# RobotCtrl_V2_Mother-board_Power.net
KiCad netlist of a schematic drawn in Altium Designer
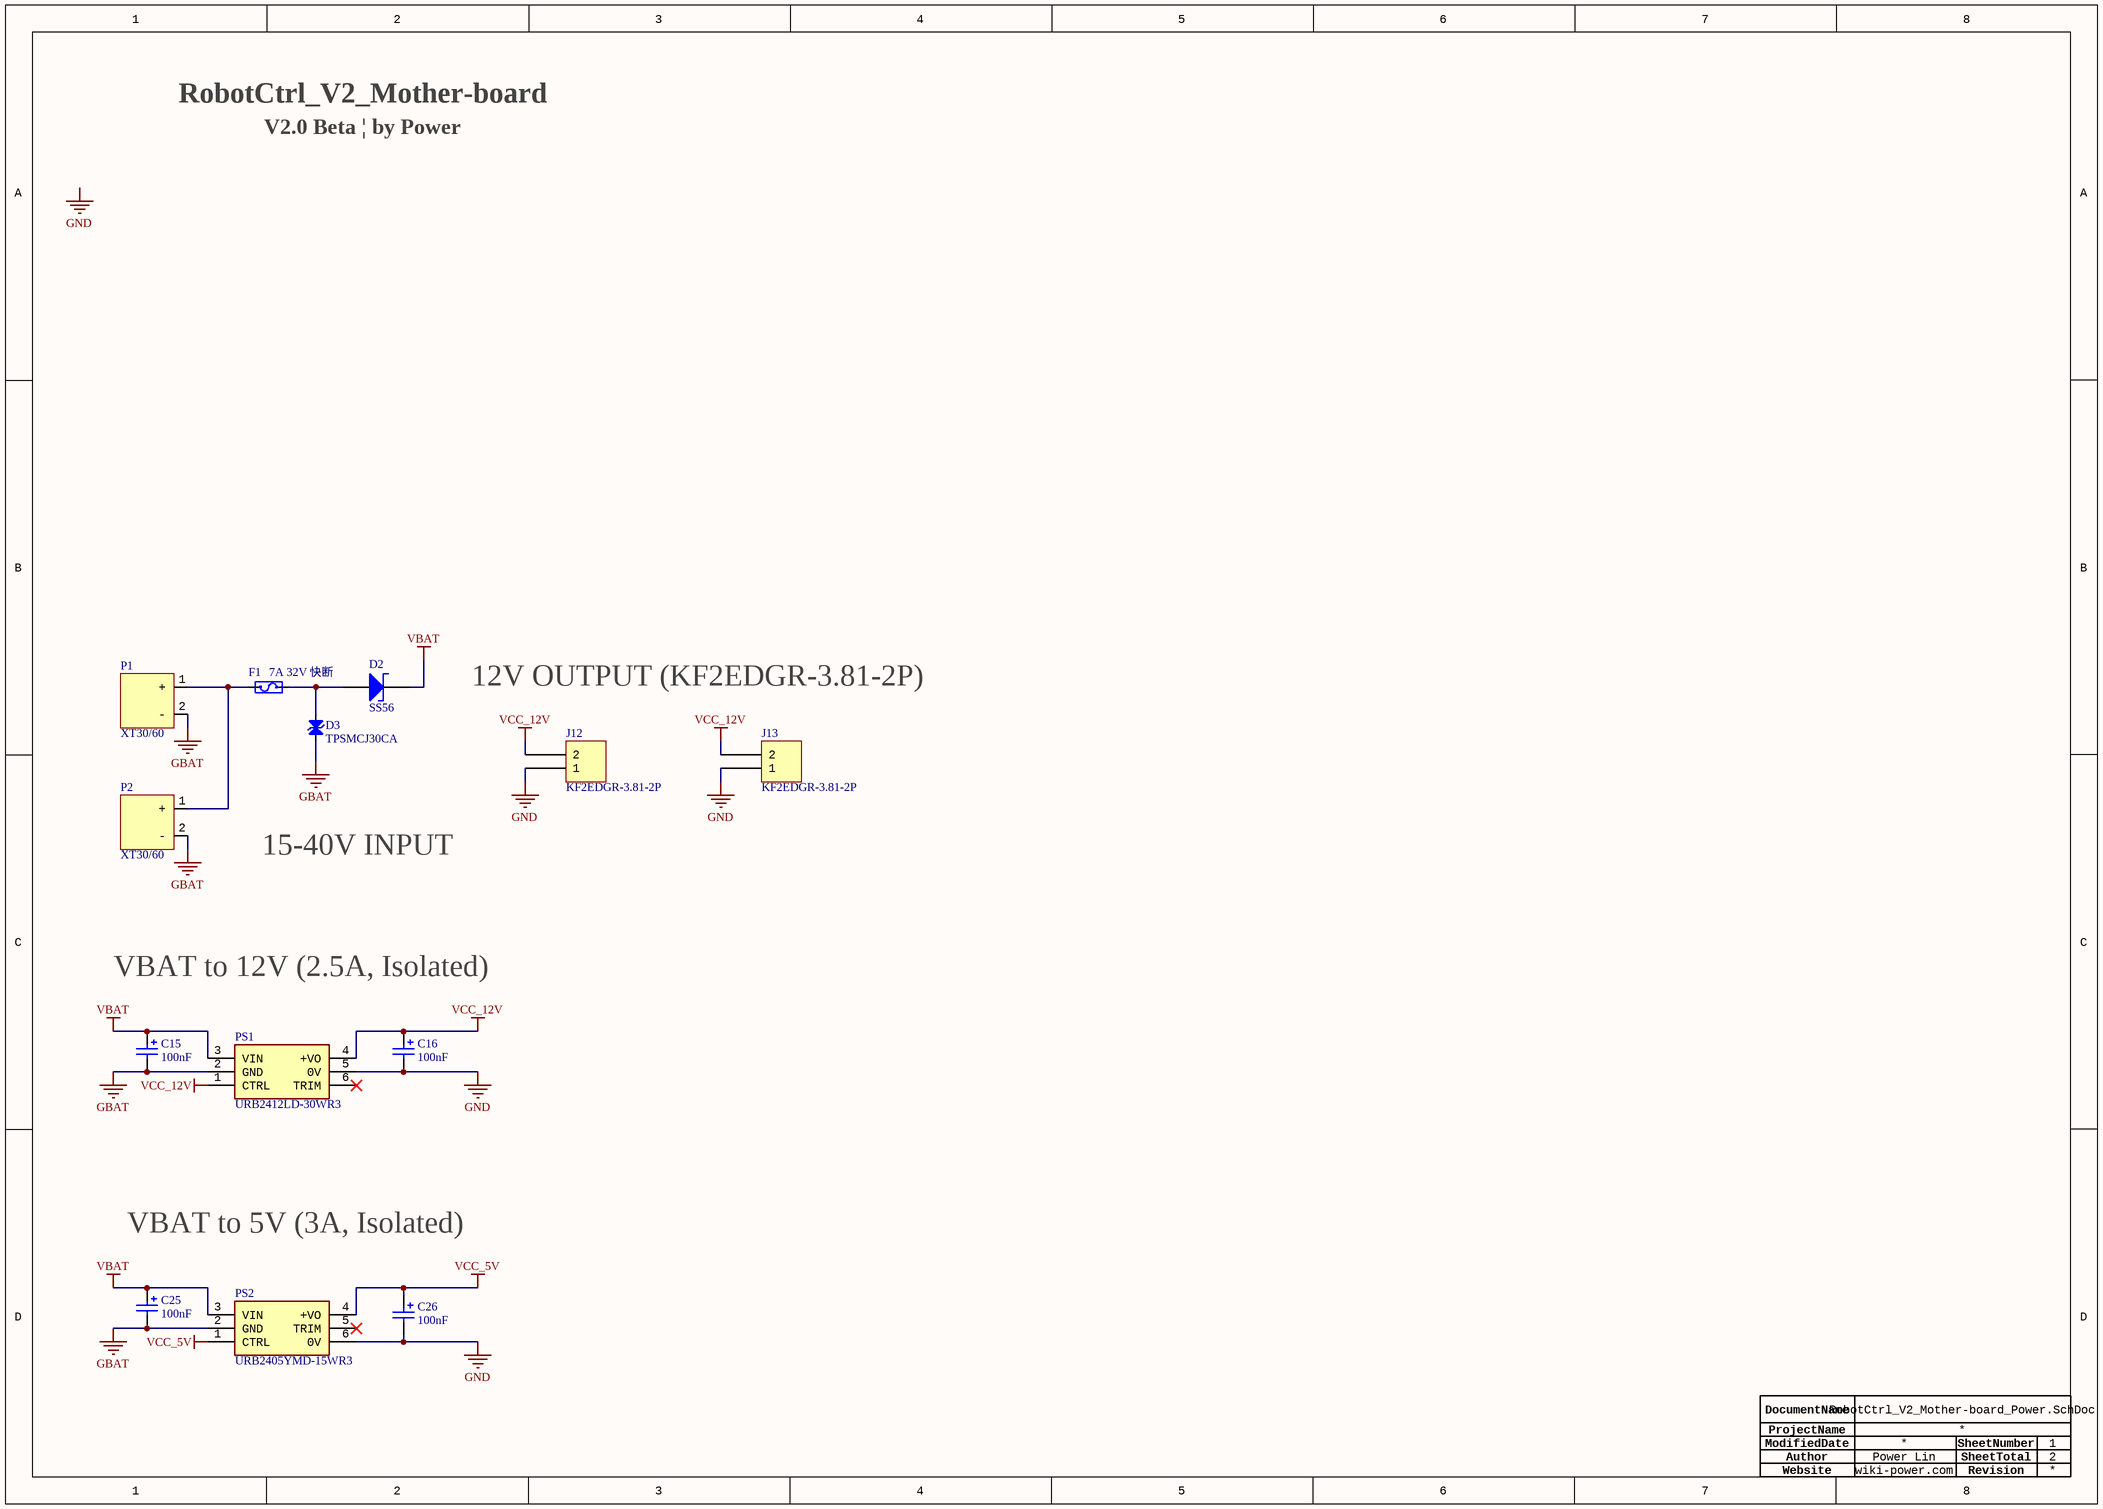
[diagram p0: RobotCtrl_V2_Mother-board_Power.SchDoc]

(export (version "E")
  (design (tool "Eeschema 10.0.6"))
  (components
    (comp (ref "C15")
      (value "100nF")
      (footprint "CAP-AUX-3216")
      (description "KM101M050F115A")
      (libsource (lib "Power_Lib_Altium") (part "CAP-POL"))
    )
    (comp (ref "C16")
      (value "100nF")
      (footprint "CAP-AUX-3216")
      (description "KM101M050F115A")
      (libsource (lib "Power_Lib_Altium") (part "CAP-POL"))
    )
    (comp (ref "C25")
      (value "100nF")
      (footprint "CAP-AUX-3216")
      (description "KM101M050F115A")
      (libsource (lib "Power_Lib_Altium") (part "CAP-POL"))
    )
    (comp (ref "C26")
      (value "100nF")
      (footprint "CAP-AUX-3216")
      (description "KM101M050F115A")
      (libsource (lib "Power_Lib_Altium") (part "CAP-POL"))
    )
    (comp (ref "D2")
      (value "SS56")
      (footprint "DO-214AB/SMC")
      (description "肖特基二极管")
      (libsource (lib "Power_Lib_Altium") (part "DIODE_Schottky"))
    )
    (comp (ref "D3")
      (value "TPSMCJ30CA")
      (footprint "DO-214AB/SMC")
      (libsource (lib "Power_Lib_Altium") (part "TVS_C"))
    )
    (comp (ref "F1")
      (value "7A 32V 快断")
      (footprint "FUSE_1206")
      (description "0437007.WR")
      (libsource (lib "Power_Lib_Altium") (part "Fuse"))
    )
    (comp (ref "J12")
      (value "KF2EDGR-3.81-2P")
      (footprint "FCI 06-381-2PIN")
      (description "TERM BLOCK HDR 2POS 90DEG 3.81MM")
      (fields (field (name "PART NUMBER") "OQ0232510000G") (field (name "MANUFACTURER") "Amphenol Anytek"))
      (libsource (lib "Power_Lib_Altium") (part "KF2EDGR-3.81-2P"))
    )
    (comp (ref "J13")
      (value "KF2EDGR-3.81-2P")
      (footprint "FCI 06-381-2PIN")
      (description "TERM BLOCK HDR 2POS 90DEG 3.81MM")
      (fields (field (name "PART NUMBER") "OQ0232510000G") (field (name "MANUFACTURER") "Amphenol Anytek"))
      (libsource (lib "Power_Lib_Altium") (part "KF2EDGR-3.81-2P"))
    )
    (comp (ref "P1")
      (value "XT30/60")
      (footprint "XT60PW-M")
      (libsource (lib "Power_Lib_Altium") (part "XT30/60"))
    )
    (comp (ref "P2")
      (value "XT30/60")
      (footprint "XT60PW-M")
      (libsource (lib "Power_Lib_Altium") (part "XT30/60"))
    )
    (comp (ref "PS1")
      (value "URB2412LD-30WR3")
      (footprint "URB2412LD30WR3")
      (description "金升阳隔离电源")
      (fields (field (name "MANUFACTURER_PART_NUMBER") "URB2412LD-30WHR3"))
      (libsource (lib "Power_Lib_Altium") (part "URB2412LD-30WR3"))
    )
    (comp (ref "PS2")
      (value "URB2405YMD-15WR3")
      (footprint "URB2405YMD15WR3")
      (description "金升阳隔离电源")
      (fields (field (name "MANUFACTURER_PART_NUMBER") "URB2405YMD-10WR3"))
      (libsource (lib "Power_Lib_Altium") (part "URB2405YMD-15WR3"))
    )
  )
  (nets
    (net (code "1") (name "GBAT") (class "Default")
      (node (ref "C15") (pin "2") (pinfunction "2_2") (pintype "passive"))
      (node (ref "C25") (pin "2") (pinfunction "2_2") (pintype "passive"))
      (node (ref "D3") (pin "1") (pinfunction "1_1") (pintype "passive"))
      (node (ref "P1") (pin "2") (pinfunction "-_2") (pintype "passive"))
      (node (ref "P2") (pin "2") (pinfunction "-_2") (pintype "passive"))
      (node (ref "PS1") (pin "2") (pinfunction "GND_2") (pintype "passive"))
      (node (ref "PS2") (pin "2") (pinfunction "GND_2") (pintype "passive"))
    )
    (net (code "2") (name "GND") (class "Default")
      (node (ref "C16") (pin "2") (pinfunction "2_2") (pintype "passive"))
      (node (ref "C26") (pin "2") (pinfunction "2_2") (pintype "passive"))
      (node (ref "J12") (pin "1") (pinfunction "1_1") (pintype "passive"))
      (node (ref "J13") (pin "1") (pinfunction "1_1") (pintype "passive"))
      (node (ref "PS1") (pin "5") (pinfunction "0V_5") (pintype "passive"))
      (node (ref "PS2") (pin "6") (pinfunction "0V_6") (pintype "passive"))
    )
    (net (code "3") (name "Net-(D2-A)") (class "Default")
      (node (ref "D2") (pin "1") (pinfunction "A_1") (pintype "passive"))
      (node (ref "D3") (pin "2") (pinfunction "2_2") (pintype "passive"))
      (node (ref "F1") (pin "2") (pinfunction "2_2") (pintype "passive"))
    )
    (net (code "4") (name "Net-(P1-+)") (class "Default")
      (node (ref "F1") (pin "1") (pinfunction "1_1") (pintype "passive"))
      (node (ref "P1") (pin "1") (pinfunction "+_1") (pintype "passive"))
      (node (ref "P2") (pin "1") (pinfunction "+_1") (pintype "passive"))
    )
    (net (code "5") (name "VBAT") (class "Default")
      (node (ref "C15") (pin "1") (pinfunction "1_1") (pintype "passive"))
      (node (ref "C25") (pin "1") (pinfunction "1_1") (pintype "passive"))
      (node (ref "D2") (pin "2") (pinfunction "K_2") (pintype "passive"))
      (node (ref "PS1") (pin "3") (pinfunction "VIN_3") (pintype "passive"))
      (node (ref "PS2") (pin "3") (pinfunction "VIN_3") (pintype "passive"))
    )
    (net (code "6") (name "VCC_5V") (class "Default")
      (node (ref "C26") (pin "1") (pinfunction "1_1") (pintype "passive"))
      (node (ref "PS2") (pin "1") (pinfunction "CTRL_1") (pintype "passive"))
      (node (ref "PS2") (pin "4") (pinfunction "+VO_4") (pintype "passive"))
    )
    (net (code "7") (name "VCC_12V") (class "Default")
      (node (ref "C16") (pin "1") (pinfunction "1_1") (pintype "passive"))
      (node (ref "J12") (pin "2") (pinfunction "2_2") (pintype "passive"))
      (node (ref "J13") (pin "2") (pinfunction "2_2") (pintype "passive"))
      (node (ref "PS1") (pin "1") (pinfunction "CTRL_1") (pintype "passive"))
      (node (ref "PS1") (pin "4") (pinfunction "+VO_4") (pintype "passive"))
    )
    (net (code "8") (name "unconnected-(PS1-TRIM-Pad6)") (class "Default")
      (node (ref "PS1") (pin "6") (pinfunction "TRIM_6") (pintype "passive+no_connect"))
    )
    (net (code "9") (name "unconnected-(PS2-TRIM-Pad5)") (class "Default")
      (node (ref "PS2") (pin "5") (pinfunction "TRIM_5") (pintype "passive+no_connect"))
    )
  )
)
